# Sheet1.net
KiCad netlist of a schematic drawn in Altium Designer
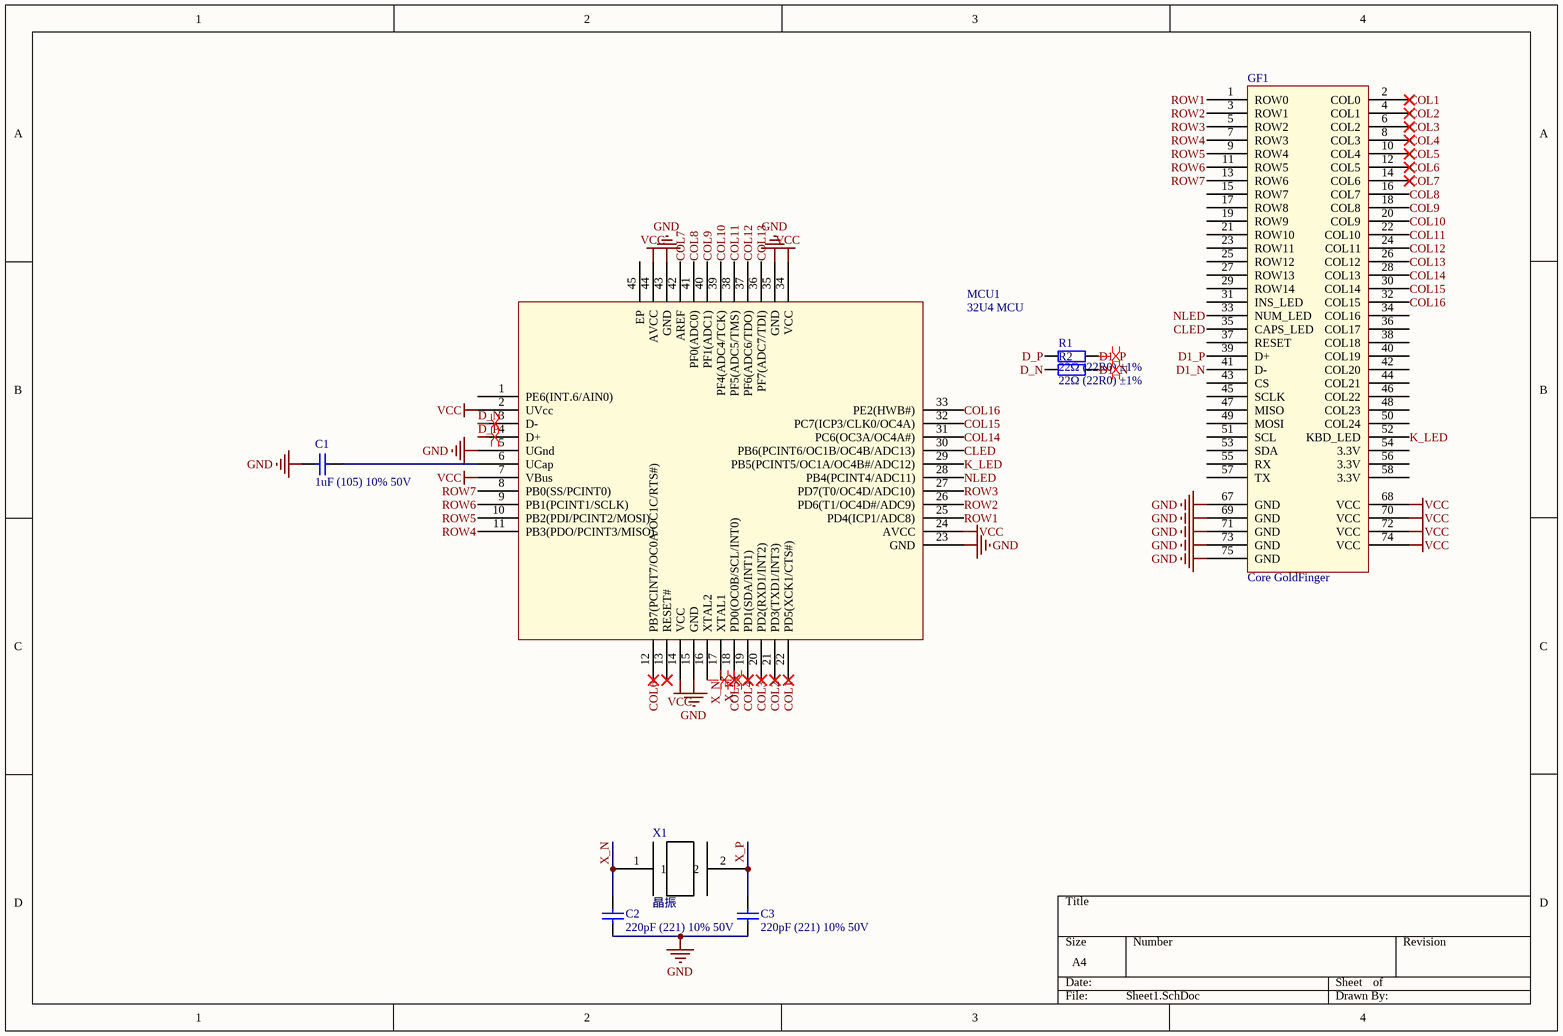
[diagram p0: Sheet1.SchDoc]

(export (version "E")
  (design (tool "Eeschema 10.0.6"))
  (components
    (comp (ref "C1")
      (value "1uF (105) 10% 50V")
      (footprint "1206_C")
      (description "贴片电容")
      (libsource (lib "Miscellaneous Devices LC") (part "1206 1uF (105) 10% 50V"))
    )
    (comp (ref "C2")
      (value "220pF (221) 10% 50V")
      (footprint "1206_C")
      (description "贴片电容")
      (libsource (lib "Miscellaneous Devices LC") (part "1206 220pF (221) 10% 50V"))
    )
    (comp (ref "C3")
      (value "220pF (221) 10% 50V")
      (footprint "1206_C")
      (description "贴片电容")
      (libsource (lib "Miscellaneous Devices LC") (part "1206 220pF (221) 10% 50V"))
    )
    (comp (ref "GF1")
      (value "Core GoldFinger")
      (footprint "Core GoldFinger")
      (libsource (lib "keyboradLib") (part "Core GoldFinger"))
    )
    (comp (ref "MCU1")
      (value "32U4 MCU")
      (footprint "32U4")
      (libsource (lib "keyboradLib") (part "32U4 MCU"))
    )
    (comp (ref "R1")
      (value "22Ω (22R0) ±1%")
      (footprint "1206_R")
      (description "贴片电阻")
      (libsource (lib "Miscellaneous Devices LC") (part "1206 22Ω (22R0) 1%"))
    )
    (comp (ref "R2")
      (value "22Ω (22R0) ±1%")
      (footprint "1206_R")
      (description "贴片电阻")
      (libsource (lib "Miscellaneous Devices LC") (part "1206 22Ω (22R0) 1%"))
    )
    (comp (ref "X1") (value "晶振") (footprint "OSC-SMD_2P-L5.0-W3.2") (libsource (lib "laptop") (part "晶振")))
  )
  (nets
    (net (code "1") (name "/CLED") (class "Default")
      (node (ref "GF1") (pin "35") (pinfunction "CAPS_LED_35") (pintype "passive"))
      (node (ref "MCU1") (pin "30") (pinfunction "PB6(PCINT6/OC1B/OC4B/ADC13)_30") (pintype "passive"))
    )
    (net (code "2") (name "/COL1") (class "Default")
      (node (ref "GF1") (pin "2") (pinfunction "COL0_2") (pintype "passive"))
      (node (ref "MCU1") (pin "22") (pinfunction "PD5(XCK1/CTS#)_22") (pintype "passive"))
    )
    (net (code "3") (name "/COL2") (class "Default")
      (node (ref "GF1") (pin "4") (pinfunction "COL1_4") (pintype "passive"))
      (node (ref "MCU1") (pin "21") (pinfunction "PD3(TXD1/INT3)_21") (pintype "passive"))
    )
    (net (code "4") (name "/COL3") (class "Default")
      (node (ref "GF1") (pin "6") (pinfunction "COL2_6") (pintype "passive"))
      (node (ref "MCU1") (pin "20") (pinfunction "PD2(RXD1/INT2)_20") (pintype "passive"))
    )
    (net (code "5") (name "/COL4") (class "Default")
      (node (ref "GF1") (pin "8") (pinfunction "COL3_8") (pintype "passive"))
      (node (ref "MCU1") (pin "19") (pinfunction "PD1(SDA/INT1)_19") (pintype "passive"))
    )
    (net (code "6") (name "/COL5") (class "Default")
      (node (ref "GF1") (pin "10") (pinfunction "COL4_10") (pintype "passive"))
      (node (ref "MCU1") (pin "18") (pinfunction "PD0(OC0B/SCL/INT0)_18") (pintype "passive"))
    )
    (net (code "7") (name "/COL6") (class "Default")
      (node (ref "GF1") (pin "12") (pinfunction "COL5_12") (pintype "passive"))
      (node (ref "MCU1") (pin "12") (pinfunction "PB7(PCINT7/OC0A/OC1C/RTS#)_12") (pintype "passive"))
    )
    (net (code "8") (name "/COL7") (class "Default")
      (node (ref "GF1") (pin "14") (pinfunction "COL6_14") (pintype "passive"))
      (node (ref "MCU1") (pin "42") (pinfunction "AREF_42") (pintype "passive"))
    )
    (net (code "9") (name "/COL8") (class "Default")
      (node (ref "GF1") (pin "16") (pinfunction "COL7_16") (pintype "passive"))
      (node (ref "MCU1") (pin "41") (pinfunction "PF0(ADC0)_41") (pintype "passive"))
    )
    (net (code "10") (name "/COL9") (class "Default")
      (node (ref "GF1") (pin "18") (pinfunction "COL8_18") (pintype "passive"))
      (node (ref "MCU1") (pin "40") (pinfunction "PF1(ADC1)_40") (pintype "passive"))
    )
    (net (code "11") (name "/COL10") (class "Default")
      (node (ref "GF1") (pin "20") (pinfunction "COL9_20") (pintype "passive"))
      (node (ref "MCU1") (pin "39") (pinfunction "PF4(ADC4/TCK)_39") (pintype "passive"))
    )
    (net (code "12") (name "/COL11") (class "Default")
      (node (ref "GF1") (pin "22") (pinfunction "COL10_22") (pintype "passive"))
      (node (ref "MCU1") (pin "38") (pinfunction "PF5(ADC5/TMS)_38") (pintype "passive"))
    )
    (net (code "13") (name "/COL12") (class "Default")
      (node (ref "GF1") (pin "24") (pinfunction "COL11_24") (pintype "passive"))
      (node (ref "MCU1") (pin "37") (pinfunction "PF6(ADC6/TDO)_37") (pintype "passive"))
    )
    (net (code "14") (name "/COL13") (class "Default")
      (node (ref "GF1") (pin "26") (pinfunction "COL12_26") (pintype "passive"))
      (node (ref "MCU1") (pin "36") (pinfunction "PF7(ADC7/TDI)_36") (pintype "passive"))
    )
    (net (code "15") (name "/COL14") (class "Default")
      (node (ref "GF1") (pin "28") (pinfunction "COL13_28") (pintype "passive"))
      (node (ref "MCU1") (pin "31") (pinfunction "PC6(OC3A/OC4A#)_31") (pintype "passive"))
    )
    (net (code "16") (name "/COL15") (class "Default")
      (node (ref "GF1") (pin "30") (pinfunction "COL14_30") (pintype "passive"))
      (node (ref "MCU1") (pin "32") (pinfunction "PC7(ICP3/CLK0/OC4A)_32") (pintype "passive"))
    )
    (net (code "17") (name "/COL16") (class "Default")
      (node (ref "GF1") (pin "32") (pinfunction "COL15_32") (pintype "passive"))
      (node (ref "MCU1") (pin "33") (pinfunction "PE2(HWB#)_33") (pintype "passive"))
    )
    (net (code "18") (name "/D1_N") (class "Default")
      (node (ref "GF1") (pin "41") (pinfunction "D-_41") (pintype "passive"))
      (node (ref "R2") (pin "2") (pinfunction "2_2") (pintype "passive"))
    )
    (net (code "19") (name "/D1_P") (class "Default")
      (node (ref "GF1") (pin "39") (pinfunction "D+_39") (pintype "passive"))
      (node (ref "R1") (pin "2") (pinfunction "2_2") (pintype "passive"))
    )
    (net (code "20") (name "/D_N") (class "Default")
      (node (ref "MCU1") (pin "3") (pinfunction "D-_3") (pintype "passive"))
      (node (ref "R2") (pin "1") (pinfunction "1_1") (pintype "passive"))
    )
    (net (code "21") (name "/D_P") (class "Default")
      (node (ref "MCU1") (pin "4") (pinfunction "D+_4") (pintype "passive"))
      (node (ref "R1") (pin "1") (pinfunction "1_1") (pintype "passive"))
    )
    (net (code "22") (name "/K_LED") (class "Default")
      (node (ref "GF1") (pin "52") (pinfunction "KBD_LED_52") (pintype "passive"))
      (node (ref "MCU1") (pin "29") (pinfunction "PB5(PCINT5/OC1A/OC4B#/ADC12)_29") (pintype "passive"))
    )
    (net (code "23") (name "/NLED") (class "Default")
      (node (ref "GF1") (pin "33") (pinfunction "NUM_LED_33") (pintype "passive"))
      (node (ref "MCU1") (pin "28") (pinfunction "PB4(PCINT4/ADC11)_28") (pintype "passive"))
    )
    (net (code "24") (name "/ROW1") (class "Default")
      (node (ref "GF1") (pin "1") (pinfunction "ROW0_1") (pintype "passive"))
      (node (ref "MCU1") (pin "25") (pinfunction "PD4(ICP1/ADC8)_25") (pintype "passive"))
    )
    (net (code "25") (name "/ROW2") (class "Default")
      (node (ref "GF1") (pin "3") (pinfunction "ROW1_3") (pintype "passive"))
      (node (ref "MCU1") (pin "26") (pinfunction "PD6(T1/OC4D#/ADC9)_26") (pintype "passive"))
    )
    (net (code "26") (name "/ROW3") (class "Default")
      (node (ref "GF1") (pin "5") (pinfunction "ROW2_5") (pintype "passive"))
      (node (ref "MCU1") (pin "27") (pinfunction "PD7(T0/OC4D/ADC10)_27") (pintype "passive"))
    )
    (net (code "27") (name "/ROW4") (class "Default")
      (node (ref "GF1") (pin "7") (pinfunction "ROW3_7") (pintype "passive"))
      (node (ref "MCU1") (pin "11") (pinfunction "PB3(PDO/PCINT3/MISO)_11") (pintype "passive"))
    )
    (net (code "28") (name "/ROW5") (class "Default")
      (node (ref "GF1") (pin "9") (pinfunction "ROW4_9") (pintype "passive"))
      (node (ref "MCU1") (pin "10") (pinfunction "PB2(PDI/PCINT2/MOSI)_10") (pintype "passive"))
    )
    (net (code "29") (name "/ROW6") (class "Default")
      (node (ref "GF1") (pin "11") (pinfunction "ROW5_11") (pintype "passive"))
      (node (ref "MCU1") (pin "9") (pinfunction "PB1(PCINT1/SCLK)_9") (pintype "passive"))
    )
    (net (code "30") (name "/ROW7") (class "Default")
      (node (ref "GF1") (pin "13") (pinfunction "ROW6_13") (pintype "passive"))
      (node (ref "MCU1") (pin "8") (pinfunction "PB0(SS/PCINT0)_8") (pintype "passive"))
    )
    (net (code "31") (name "/X_N") (class "Default")
      (node (ref "C2") (pin "2") (pinfunction "2_2") (pintype "passive"))
      (node (ref "MCU1") (pin "16") (pinfunction "XTAL2_16") (pintype "passive"))
      (node (ref "X1") (pin "1") (pinfunction "1_1") (pintype "passive"))
    )
    (net (code "32") (name "/X_P") (class "Default")
      (node (ref "C3") (pin "2") (pinfunction "2_2") (pintype "passive"))
      (node (ref "MCU1") (pin "17") (pinfunction "XTAL1_17") (pintype "passive"))
      (node (ref "X1") (pin "2") (pinfunction "2_2") (pintype "passive"))
    )
    (net (code "33") (name "GND") (class "Default")
      (node (ref "C1") (pin "1") (pinfunction "1_1") (pintype "passive"))
      (node (ref "C2") (pin "1") (pinfunction "1_1") (pintype "passive"))
      (node (ref "C3") (pin "1") (pinfunction "1_1") (pintype "passive"))
      (node (ref "GF1") (pin "67") (pinfunction "GND_67") (pintype "passive"))
      (node (ref "GF1") (pin "69") (pinfunction "GND_69") (pintype "passive"))
      (node (ref "GF1") (pin "71") (pinfunction "GND_71") (pintype "passive"))
      (node (ref "GF1") (pin "73") (pinfunction "GND_73") (pintype "passive"))
      (node (ref "GF1") (pin "75") (pinfunction "GND_75") (pintype "passive"))
      (node (ref "MCU1") (pin "15") (pinfunction "GND_15") (pintype "passive"))
      (node (ref "MCU1") (pin "23") (pinfunction "GND_23") (pintype "passive"))
      (node (ref "MCU1") (pin "35") (pinfunction "GND_35") (pintype "passive"))
      (node (ref "MCU1") (pin "43") (pinfunction "GND_43") (pintype "passive"))
      (node (ref "MCU1") (pin "5") (pinfunction "UGnd_5") (pintype "passive"))
    )
    (net (code "34") (name "Net-(MCU1-UCap)") (class "Default")
      (node (ref "C1") (pin "2") (pinfunction "2_2") (pintype "passive"))
      (node (ref "MCU1") (pin "6") (pinfunction "UCap_6") (pintype "passive"))
    )
    (net (code "35") (name "VCC") (class "Default")
      (node (ref "GF1") (pin "68") (pinfunction "VCC_68") (pintype "passive"))
      (node (ref "GF1") (pin "70") (pinfunction "VCC_70") (pintype "passive"))
      (node (ref "GF1") (pin "72") (pinfunction "VCC_72") (pintype "passive"))
      (node (ref "GF1") (pin "74") (pinfunction "VCC_74") (pintype "passive"))
      (node (ref "MCU1") (pin "14") (pinfunction "VCC_14") (pintype "passive"))
      (node (ref "MCU1") (pin "2") (pinfunction "UVcc_2") (pintype "passive"))
      (node (ref "MCU1") (pin "24") (pinfunction "AVCC_24") (pintype "passive"))
      (node (ref "MCU1") (pin "34") (pinfunction "VCC_34") (pintype "passive"))
      (node (ref "MCU1") (pin "44") (pinfunction "AVCC_44") (pintype "passive"))
      (node (ref "MCU1") (pin "7") (pinfunction "VBus_7") (pintype "passive"))
    )
    (net (code "36") (name "unconnected-(GF1-3.3V-Pad54)") (class "Default")
      (node (ref "GF1") (pin "54") (pinfunction "3.3V_54") (pintype "passive"))
    )
    (net (code "37") (name "unconnected-(GF1-3.3V-Pad56)") (class "Default")
      (node (ref "GF1") (pin "56") (pinfunction "3.3V_56") (pintype "passive"))
    )
    (net (code "38") (name "unconnected-(GF1-3.3V-Pad58)") (class "Default")
      (node (ref "GF1") (pin "58") (pinfunction "3.3V_58") (pintype "passive"))
    )
    (net (code "39") (name "unconnected-(GF1-COL16-Pad34)") (class "Default")
      (node (ref "GF1") (pin "34") (pinfunction "COL16_34") (pintype "passive"))
    )
    (net (code "40") (name "unconnected-(GF1-COL17-Pad36)") (class "Default")
      (node (ref "GF1") (pin "36") (pinfunction "COL17_36") (pintype "passive"))
    )
    (net (code "41") (name "unconnected-(GF1-COL18-Pad38)") (class "Default")
      (node (ref "GF1") (pin "38") (pinfunction "COL18_38") (pintype "passive"))
    )
    (net (code "42") (name "unconnected-(GF1-COL19-Pad40)") (class "Default")
      (node (ref "GF1") (pin "40") (pinfunction "COL19_40") (pintype "passive"))
    )
    (net (code "43") (name "unconnected-(GF1-COL20-Pad42)") (class "Default")
      (node (ref "GF1") (pin "42") (pinfunction "COL20_42") (pintype "passive"))
    )
    (net (code "44") (name "unconnected-(GF1-COL21-Pad44)") (class "Default")
      (node (ref "GF1") (pin "44") (pinfunction "COL21_44") (pintype "passive"))
    )
    (net (code "45") (name "unconnected-(GF1-COL22-Pad46)") (class "Default")
      (node (ref "GF1") (pin "46") (pinfunction "COL22_46") (pintype "passive"))
    )
    (net (code "46") (name "unconnected-(GF1-COL23-Pad48)") (class "Default")
      (node (ref "GF1") (pin "48") (pinfunction "COL23_48") (pintype "passive"))
    )
    (net (code "47") (name "unconnected-(GF1-COL24-Pad50)") (class "Default")
      (node (ref "GF1") (pin "50") (pinfunction "COL24_50") (pintype "passive"))
    )
    (net (code "48") (name "unconnected-(GF1-CS-Pad43)") (class "Default")
      (node (ref "GF1") (pin "43") (pinfunction "CS_43") (pintype "passive"))
    )
    (net (code "49") (name "unconnected-(GF1-INS_LED-Pad31)") (class "Default")
      (node (ref "GF1") (pin "31") (pinfunction "INS_LED_31") (pintype "passive"))
    )
    (net (code "50") (name "unconnected-(GF1-MISO-Pad47)") (class "Default")
      (node (ref "GF1") (pin "47") (pinfunction "MISO_47") (pintype "passive"))
    )
    (net (code "51") (name "unconnected-(GF1-MOSI-Pad49)") (class "Default")
      (node (ref "GF1") (pin "49") (pinfunction "MOSI_49") (pintype "passive"))
    )
    (net (code "52") (name "unconnected-(GF1-RESET-Pad37)") (class "Default")
      (node (ref "GF1") (pin "37") (pinfunction "RESET_37") (pintype "passive"))
    )
    (net (code "53") (name "unconnected-(GF1-ROW7-Pad15)") (class "Default")
      (node (ref "GF1") (pin "15") (pinfunction "ROW7_15") (pintype "passive"))
    )
    (net (code "54") (name "unconnected-(GF1-ROW8-Pad17)") (class "Default")
      (node (ref "GF1") (pin "17") (pinfunction "ROW8_17") (pintype "passive"))
    )
    (net (code "55") (name "unconnected-(GF1-ROW9-Pad19)") (class "Default")
      (node (ref "GF1") (pin "19") (pinfunction "ROW9_19") (pintype "passive"))
    )
    (net (code "56") (name "unconnected-(GF1-ROW10-Pad21)") (class "Default")
      (node (ref "GF1") (pin "21") (pinfunction "ROW10_21") (pintype "passive"))
    )
    (net (code "57") (name "unconnected-(GF1-ROW11-Pad23)") (class "Default")
      (node (ref "GF1") (pin "23") (pinfunction "ROW11_23") (pintype "passive"))
    )
    (net (code "58") (name "unconnected-(GF1-ROW12-Pad25)") (class "Default")
      (node (ref "GF1") (pin "25") (pinfunction "ROW12_25") (pintype "passive"))
    )
    (net (code "59") (name "unconnected-(GF1-ROW13-Pad27)") (class "Default")
      (node (ref "GF1") (pin "27") (pinfunction "ROW13_27") (pintype "passive"))
    )
    (net (code "60") (name "unconnected-(GF1-ROW14-Pad29)") (class "Default")
      (node (ref "GF1") (pin "29") (pinfunction "ROW14_29") (pintype "passive"))
    )
    (net (code "61") (name "unconnected-(GF1-RX-Pad55)") (class "Default")
      (node (ref "GF1") (pin "55") (pinfunction "RX_55") (pintype "passive"))
    )
    (net (code "62") (name "unconnected-(GF1-SCL-Pad51)") (class "Default")
      (node (ref "GF1") (pin "51") (pinfunction "SCL_51") (pintype "passive"))
    )
    (net (code "63") (name "unconnected-(GF1-SCLK-Pad45)") (class "Default")
      (node (ref "GF1") (pin "45") (pinfunction "SCLK_45") (pintype "passive"))
    )
    (net (code "64") (name "unconnected-(GF1-SDA-Pad53)") (class "Default")
      (node (ref "GF1") (pin "53") (pinfunction "SDA_53") (pintype "passive"))
    )
    (net (code "65") (name "unconnected-(GF1-TX-Pad57)") (class "Default")
      (node (ref "GF1") (pin "57") (pinfunction "TX_57") (pintype "passive"))
    )
    (net (code "66") (name "unconnected-(MCU1-EP-Pad45)") (class "Default")
      (node (ref "MCU1") (pin "45") (pinfunction "EP_45") (pintype "passive"))
    )
    (net (code "67") (name "unconnected-(MCU1-PE6(INT.6{slash}AIN0)-Pad1)") (class "Default")
      (node (ref "MCU1") (pin "1") (pinfunction "PE6(INT.6/AIN0)_1") (pintype "passive"))
    )
    (net (code "68") (name "unconnected-(MCU1-RESET#-Pad13)") (class "Default")
      (node (ref "MCU1") (pin "13") (pinfunction "RESET#_13") (pintype "passive+no_connect"))
    )
  )
)
